# Placa_de_processamento.net
KiCad netlist of a schematic drawn in EAGLE
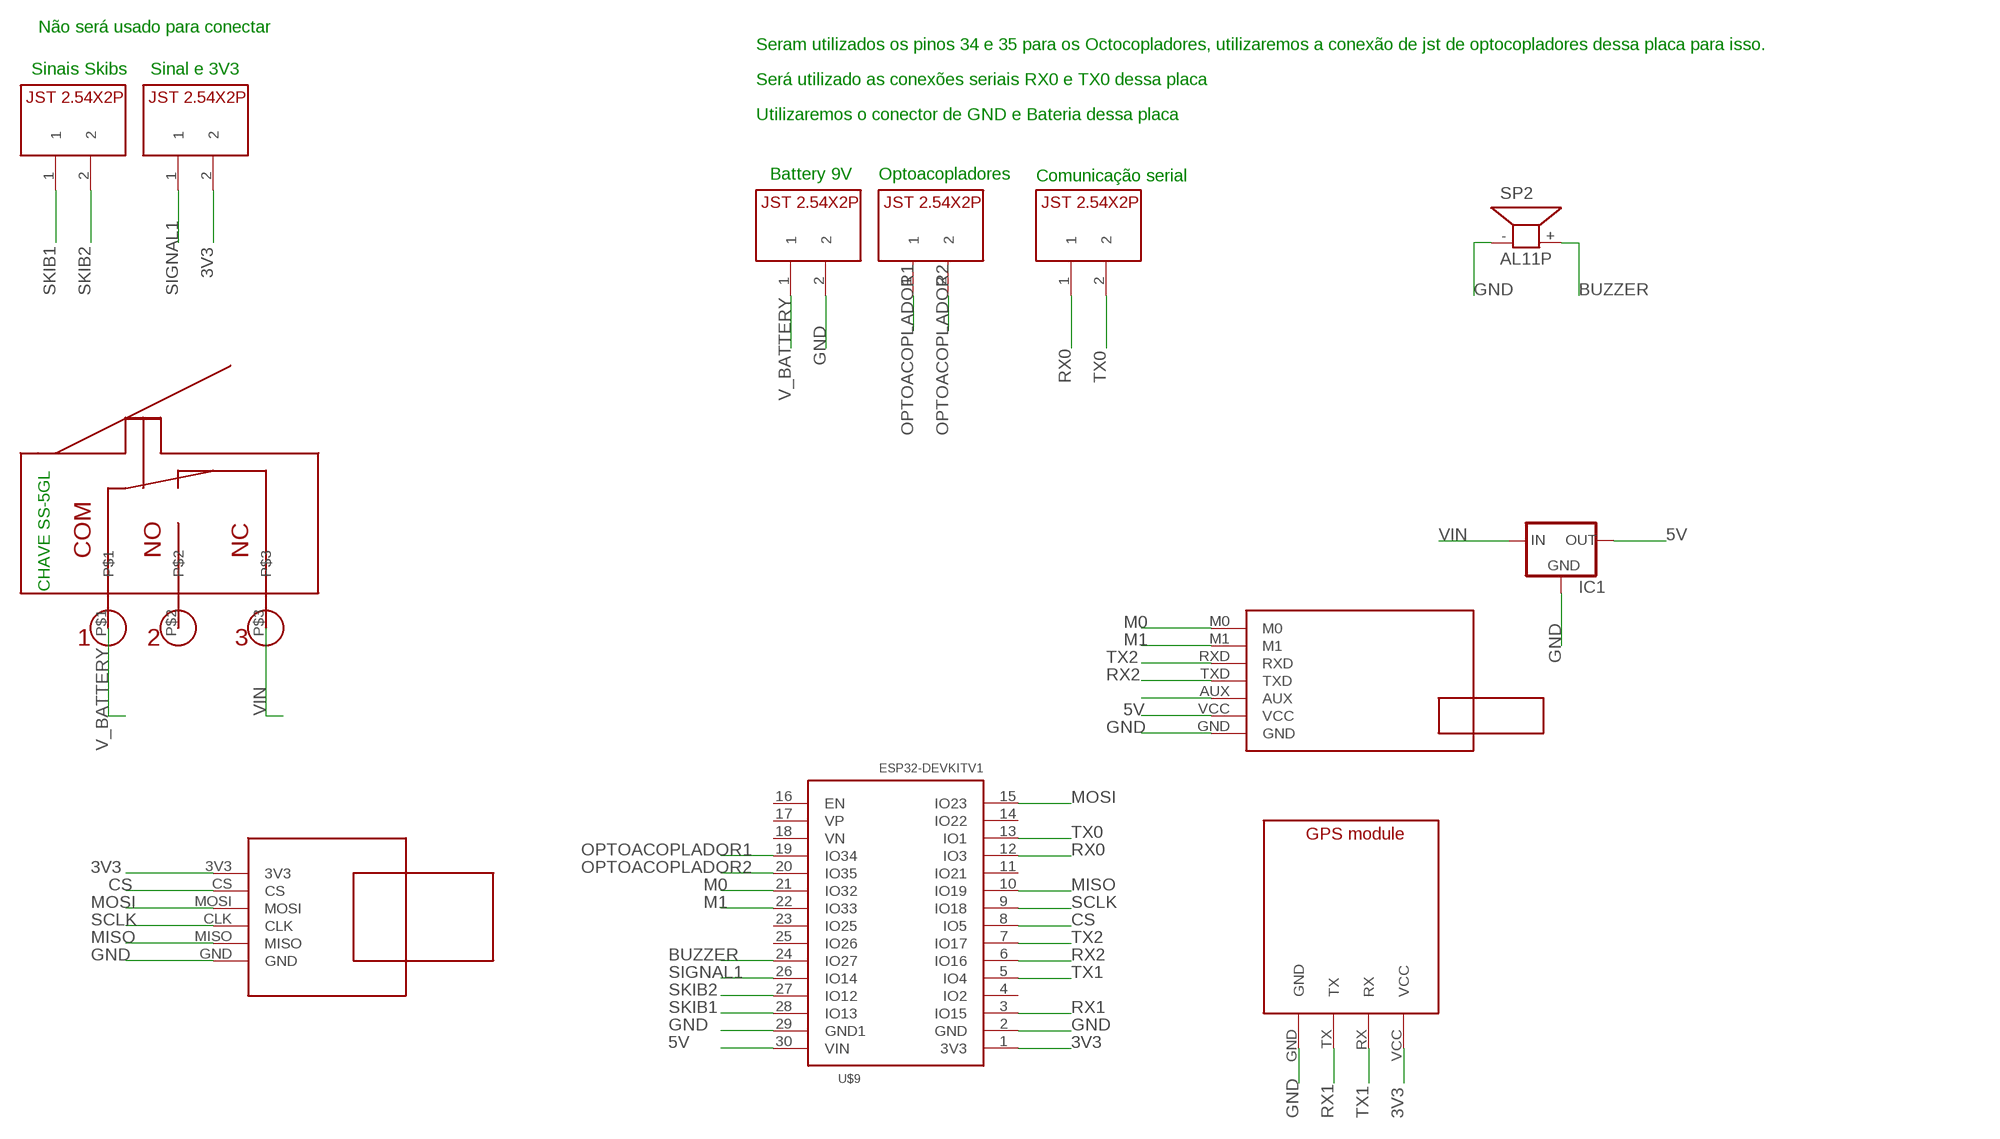
[diagram p0: schematic, sheet 1]

(export (version "E")
  (design (tool "Eeschema 10.0.6"))
  (components
    (comp (ref "IC1")
      (value "78XXL")
      (footprint "eagle-import:78XXL")
      (libsource (lib "eagle-import") (part "78XXL"))
    )
    (comp (ref "SP2")
      (value "AL11P")
      (footprint "eagle-import:AL11P")
      (libsource (lib "eagle-import") (part "AL11P"))
    )
    (comp (ref "U$2")
      (value "MICROSD_SMALL_READER")
      (footprint "eagle-import:MICROSD_SMALL_READER_FOOTPRINT")
      (libsource (lib "eagle-import") (part "MICROSD_SMALL_READER"))
    )
    (comp (ref "U$3")
      (value "JST2.54X2P")
      (footprint "eagle-import:JST2.54X2P_FOOTPRINT")
      (libsource (lib "eagle-import") (part "JST2.54X2P"))
    )
    (comp (ref "U$4")
      (value "JST2.54X2P")
      (footprint "eagle-import:JST2.54X2P_FOOTPRINT")
      (libsource (lib "eagle-import") (part "JST2.54X2P"))
    )
    (comp (ref "U$5")
      (value "JST2.54X2P")
      (footprint "eagle-import:JST2.54X2P_FOOTPRINT")
      (libsource (lib "eagle-import") (part "JST2.54X2P"))
    )
    (comp (ref "U$6")
      (value "JST2.54X2P")
      (footprint "eagle-import:JST2.54X2P_FOOTPRINT")
      (libsource (lib "eagle-import") (part "JST2.54X2P"))
    )
    (comp (ref "U$7")
      (value "GPS_MODULE")
      (footprint "eagle-import:GPS_MODULE_FOOTPRINT")
      (libsource (lib "eagle-import") (part "GPS_MODULE"))
    )
    (comp (ref "U$8")
      (value "E22-400T30D")
      (footprint "eagle-import:E22-400T30D_FOOTPRINT")
      (libsource (lib "eagle-import") (part "E22-400T30D"))
    )
    (comp (ref "U$9")
      (value "ESP32DEVKITV1")
      (footprint "eagle-import:ESP32-DEVKITV1")
      (libsource (lib "eagle-import") (part "ESP32DEVKITV1"))
    )
    (comp (ref "U$10")
      (value "JST2.54X2P")
      (footprint "eagle-import:JST2.54X2P_FOOTPRINT")
      (libsource (lib "eagle-import") (part "JST2.54X2P"))
    )
    (comp (ref "U$11")
      (value "CHAVE_SS-5GL")
      (footprint "eagle-import:CHAVESS-5GL")
      (libsource (lib "eagle-import") (part "CHAVE_SS-5GL"))
    )
  )
  (nets
    (net (code "1") (name "/3V3") (class "Default")
      (node (ref "U$2") (pin "3V3") (pinfunction "3V3_3V3") (pintype "bidirectional"))
      (node (ref "U$5") (pin "2") (pinfunction "2_2") (pintype "bidirectional"))
      (node (ref "U$7") (pin "VCC") (pinfunction "VCC_VCC") (pintype "bidirectional"))
      (node (ref "U$9") (pin "1") (pinfunction "3V3_1") (pintype "bidirectional"))
    )
    (net (code "2") (name "/5V") (class "Default")
      (node (ref "IC1") (pin "OUT") (pinfunction "OUT_OUT") (pintype "passive"))
      (node (ref "U$8") (pin "VCC") (pinfunction "VCC_VCC") (pintype "bidirectional"))
      (node (ref "U$9") (pin "30") (pinfunction "VIN_30") (pintype "bidirectional"))
    )
    (net (code "3") (name "/BUZZER") (class "Default")
      (node (ref "SP2") (pin "+") (pinfunction "2_+") (pintype "passive"))
      (node (ref "U$9") (pin "24") (pinfunction "IO27_24") (pintype "bidirectional"))
    )
    (net (code "4") (name "/CS") (class "Default")
      (node (ref "U$2") (pin "CS") (pinfunction "CS_CS") (pintype "bidirectional"))
      (node (ref "U$9") (pin "8") (pinfunction "IO5_8") (pintype "bidirectional"))
    )
    (net (code "5") (name "/GND") (class "Default")
      (node (ref "IC1") (pin "GND") (pinfunction "GND_GND") (pintype "input"))
      (node (ref "SP2") (pin "-") (pinfunction "1_-") (pintype "passive"))
      (node (ref "U$2") (pin "GND") (pinfunction "GND_GND") (pintype "bidirectional"))
      (node (ref "U$3") (pin "2") (pinfunction "2_2") (pintype "bidirectional"))
      (node (ref "U$7") (pin "GND") (pinfunction "GND_GND") (pintype "bidirectional"))
      (node (ref "U$8") (pin "GND") (pinfunction "GND_GND") (pintype "bidirectional"))
      (node (ref "U$9") (pin "2") (pinfunction "GND_2") (pintype "bidirectional"))
      (node (ref "U$9") (pin "29") (pinfunction "GND1_29") (pintype "bidirectional"))
    )
    (net (code "6") (name "/M0") (class "Default")
      (node (ref "U$8") (pin "M0") (pinfunction "M0_M0") (pintype "bidirectional"))
      (node (ref "U$9") (pin "21") (pinfunction "IO32_21") (pintype "bidirectional"))
    )
    (net (code "7") (name "/M1") (class "Default")
      (node (ref "U$8") (pin "M1") (pinfunction "M1_M1") (pintype "bidirectional"))
      (node (ref "U$9") (pin "22") (pinfunction "IO33_22") (pintype "bidirectional"))
    )
    (net (code "8") (name "/MISO") (class "Default")
      (node (ref "U$2") (pin "MISO") (pinfunction "MISO_MISO") (pintype "bidirectional"))
      (node (ref "U$9") (pin "10") (pinfunction "IO19_10") (pintype "bidirectional"))
    )
    (net (code "9") (name "/MOSI") (class "Default")
      (node (ref "U$2") (pin "MOSI") (pinfunction "MOSI_MOSI") (pintype "bidirectional"))
      (node (ref "U$9") (pin "15") (pinfunction "IO23_15") (pintype "bidirectional"))
    )
    (net (code "10") (name "/OPTOACOPLADOR1") (class "Default")
      (node (ref "U$6") (pin "1") (pinfunction "1_1") (pintype "bidirectional"))
      (node (ref "U$9") (pin "19") (pinfunction "IO34_19") (pintype "bidirectional"))
    )
    (net (code "11") (name "/OPTOACOPLADOR2") (class "Default")
      (node (ref "U$6") (pin "2") (pinfunction "2_2") (pintype "bidirectional"))
      (node (ref "U$9") (pin "20") (pinfunction "IO35_20") (pintype "bidirectional"))
    )
    (net (code "12") (name "/RX0") (class "Default")
      (node (ref "U$10") (pin "1") (pinfunction "1_1") (pintype "bidirectional"))
      (node (ref "U$9") (pin "12") (pinfunction "IO3_12") (pintype "bidirectional"))
    )
    (net (code "13") (name "/RX1") (class "Default")
      (node (ref "U$7") (pin "TX") (pinfunction "TX_TX") (pintype "bidirectional"))
      (node (ref "U$9") (pin "3") (pinfunction "IO15_3") (pintype "bidirectional"))
    )
    (net (code "14") (name "/RX2") (class "Default")
      (node (ref "U$8") (pin "TXD") (pinfunction "TXD_TXD") (pintype "bidirectional"))
      (node (ref "U$9") (pin "6") (pinfunction "IO16_6") (pintype "bidirectional"))
    )
    (net (code "15") (name "/SCLK") (class "Default")
      (node (ref "U$2") (pin "CLK") (pinfunction "CLK_CLK") (pintype "bidirectional"))
      (node (ref "U$9") (pin "9") (pinfunction "IO18_9") (pintype "bidirectional"))
    )
    (net (code "16") (name "/SIGNAL1") (class "Default")
      (node (ref "U$5") (pin "1") (pinfunction "1_1") (pintype "bidirectional"))
      (node (ref "U$9") (pin "26") (pinfunction "IO14_26") (pintype "bidirectional"))
    )
    (net (code "17") (name "/SKIB1") (class "Default")
      (node (ref "U$4") (pin "1") (pinfunction "1_1") (pintype "bidirectional"))
      (node (ref "U$9") (pin "28") (pinfunction "IO13_28") (pintype "bidirectional"))
    )
    (net (code "18") (name "/SKIB2") (class "Default")
      (node (ref "U$4") (pin "2") (pinfunction "2_2") (pintype "bidirectional"))
      (node (ref "U$9") (pin "27") (pinfunction "IO12_27") (pintype "bidirectional"))
    )
    (net (code "19") (name "/TX0") (class "Default")
      (node (ref "U$10") (pin "2") (pinfunction "2_2") (pintype "bidirectional"))
      (node (ref "U$9") (pin "13") (pinfunction "IO1_13") (pintype "bidirectional"))
    )
    (net (code "20") (name "/TX1") (class "Default")
      (node (ref "U$7") (pin "RX") (pinfunction "RX_RX") (pintype "bidirectional"))
      (node (ref "U$9") (pin "5") (pinfunction "IO4_5") (pintype "bidirectional"))
    )
    (net (code "21") (name "/TX2") (class "Default")
      (node (ref "U$8") (pin "RXD") (pinfunction "RXD_RXD") (pintype "bidirectional"))
      (node (ref "U$9") (pin "7") (pinfunction "IO17_7") (pintype "bidirectional"))
    )
    (net (code "22") (name "/VIN") (class "Default")
      (node (ref "IC1") (pin "IN") (pinfunction "IN_IN") (pintype "input"))
      (node (ref "U$11") (pin "P$3") (pinfunction "P$3_P$3") (pintype "bidirectional"))
    )
    (net (code "23") (name "/V_BATTERY") (class "Default")
      (node (ref "U$11") (pin "P$1") (pinfunction "P$1_P$1") (pintype "bidirectional"))
      (node (ref "U$3") (pin "1") (pinfunction "1_1") (pintype "bidirectional"))
    )
    (net (code "24") (name "unconnected-(U$8-PadAUX)") (class "Default")
      (node (ref "U$8") (pin "AUX") (pinfunction "AUX_AUX") (pintype "bidirectional"))
    )
    (net (code "25") (name "unconnected-(U$9-EN-Pad16)") (class "Default")
      (node (ref "U$9") (pin "16") (pinfunction "EN_16") (pintype "bidirectional"))
    )
    (net (code "26") (name "unconnected-(U$9-IO2-Pad4)") (class "Default")
      (node (ref "U$9") (pin "4") (pinfunction "IO2_4") (pintype "bidirectional"))
    )
    (net (code "27") (name "unconnected-(U$9-IO21-Pad11)") (class "Default")
      (node (ref "U$9") (pin "11") (pinfunction "IO21_11") (pintype "bidirectional"))
    )
    (net (code "28") (name "unconnected-(U$9-IO22-Pad14)") (class "Default")
      (node (ref "U$9") (pin "14") (pinfunction "IO22_14") (pintype "bidirectional"))
    )
    (net (code "29") (name "unconnected-(U$9-IO25-Pad23)") (class "Default")
      (node (ref "U$9") (pin "23") (pinfunction "IO25_23") (pintype "bidirectional"))
    )
    (net (code "30") (name "unconnected-(U$9-IO26-Pad25)") (class "Default")
      (node (ref "U$9") (pin "25") (pinfunction "IO26_25") (pintype "bidirectional"))
    )
    (net (code "31") (name "unconnected-(U$9-VN-Pad18)") (class "Default")
      (node (ref "U$9") (pin "18") (pinfunction "VN_18") (pintype "bidirectional"))
    )
    (net (code "32") (name "unconnected-(U$9-VP-Pad17)") (class "Default")
      (node (ref "U$9") (pin "17") (pinfunction "VP_17") (pintype "bidirectional"))
    )
    (net (code "33") (name "unconnected-(U$11-PadP$2)") (class "Default")
      (node (ref "U$11") (pin "P$2") (pinfunction "P$2_P$2") (pintype "bidirectional"))
    )
  )
)
